# sch.net
KiCad netlist of a schematic drawn in EAGLE
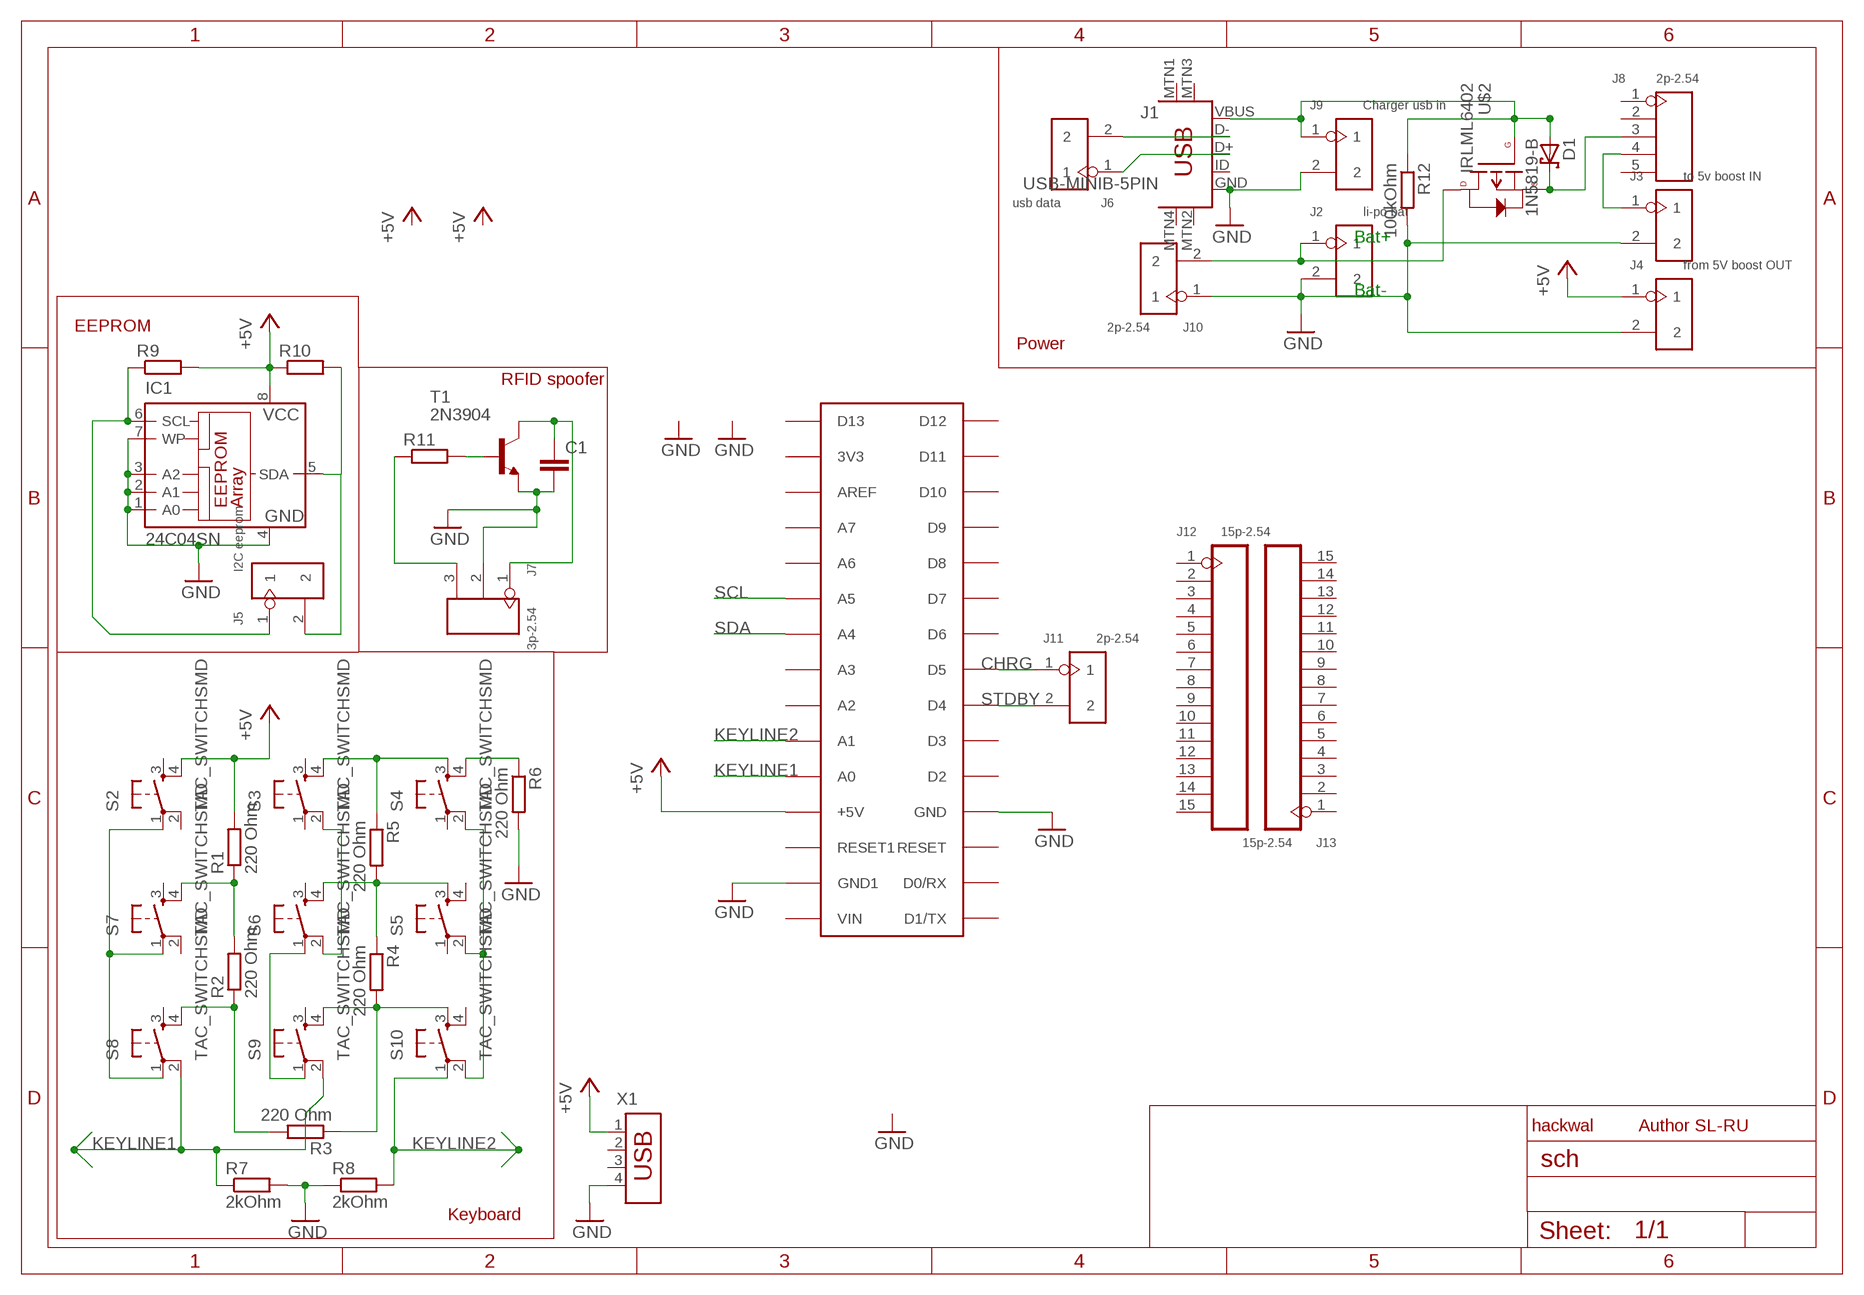
[diagram p0: schematic, sheet 1]

(export (version "E")
  (design (tool "Eeschema 10.0.6"))
  (components
    (comp (ref "C1")
      (value "C5/3")
      (footprint "eagle-import:C5B3")
      (libsource (lib "eagle-import") (part "C5/3"))
    )
    (comp (ref "D1")
      (value "1N5819-B")
      (footprint "eagle-import:DO41-7.6")
      (libsource (lib "eagle-import") (part "1N5819-B"))
    )
    (comp (ref "IC1")
      (value "24C04SN")
      (footprint "eagle-import:SO-08")
      (fields (field (name "MPN") "M24C04-WMN6P"))
      (libsource (lib "eagle-import") (part "24CSN04"))
    )
    (comp (ref "J1")
      (value "USB-MINIB-5PIN")
      (footprint "eagle-import:USB-MINIB")
      (libsource (lib "eagle-import") (part "USB-MINIB-5PIN"))
    )
    (comp (ref "J2")
      (value "li-po bat")
      (footprint "eagle-import:H2-2.54")
      (fields (field (name "MPN") "P125-1102A0BS116A1"))
      (libsource (lib "eagle-import") (part "DIP-BLACK-MALE-HEADER-VERT(2P-2.54)"))
    )
    (comp (ref "J3")
      (value "to 5v boost IN")
      (footprint "eagle-import:H2-2.54")
      (fields (field (name "MPN") "F185-1102A1BSYA1"))
      (libsource (lib "eagle-import") (part "DIP-BLACK-FEMALE-HEADER-VERT(2P-2.54)"))
    )
    (comp (ref "J4")
      (value "from 5V boost OUT")
      (footprint "eagle-import:H2-2.54")
      (fields (field (name "MPN") "F185-1102A1BSYA1"))
      (libsource (lib "eagle-import") (part "DIP-BLACK-FEMALE-HEADER-VERT(2P-2.54)"))
    )
    (comp (ref "J5")
      (value "I2C eeprom")
      (footprint "eagle-import:H2-2.54")
      (fields (field (name "MPN") "F185-1102A1BSYA1"))
      (libsource (lib "eagle-import") (part "DIP-BLACK-FEMALE-HEADER-VERT(2P-2.54)"))
    )
    (comp (ref "J6")
      (value "usb data")
      (footprint "eagle-import:H2-2.54")
      (fields (field (name "MPN") "F185-1102A1BSYA1"))
      (libsource (lib "eagle-import") (part "DIP-BLACK-FEMALE-HEADER-VERT(2P-2.54)"))
    )
    (comp (ref "J7")
      (value "3p-2.54")
      (footprint "eagle-import:H3-2.54")
      (fields (field (name "MPN") "F185-1103A0BSYA1"))
      (libsource (lib "eagle-import") (part "DIP-BLACK-FEMALE-HEADER-VERT(3P-2.54)"))
    )
    (comp (ref "J8")
      (value "2p-2.54")
      (footprint "eagle-import:H5-2.54")
      (libsource (lib "eagle-import") (part "DIP-BLACK-MALE-HEADER-VERT(5P-2.54)"))
    )
    (comp (ref "J9")
      (value "Charger usb in")
      (footprint "eagle-import:H2-2.54")
      (fields (field (name "MPN") "P125-1102A0BS116A1"))
      (libsource (lib "eagle-import") (part "DIP-BLACK-MALE-HEADER-VERT(2P-2.54)"))
    )
    (comp (ref "J10")
      (value "2p-2.54")
      (footprint "eagle-import:H2-2.54")
      (fields (field (name "MPN") "P125-1102A0BS116A1"))
      (libsource (lib "eagle-import") (part "DIP-BLACK-MALE-HEADER-VERT(2P-2.54)"))
    )
    (comp (ref "J11")
      (value "2p-2.54")
      (footprint "eagle-import:H2-2.54")
      (fields (field (name "MPN") "P125-1102A0BS116A1"))
      (libsource (lib "eagle-import") (part "DIP-BLACK-MALE-HEADER-VERT(2P-2.54)"))
    )
    (comp (ref "J12")
      (value "15p-2.54")
      (footprint "eagle-import:H15-2.54")
      (libsource (lib "eagle-import") (part "DIP-BLACK-FEMALE-HEADER-VERT(15P-2.54)"))
    )
    (comp (ref "J13")
      (value "15p-2.54")
      (footprint "eagle-import:H15-2.54")
      (libsource (lib "eagle-import") (part "DIP-BLACK-FEMALE-HEADER-VERT(15P-2.54)"))
    )
    (comp (ref "R1")
      (value "220 Ohm")
      (footprint "eagle-import:0207_10")
      (libsource (lib "eagle-import") (part "R-EU_0207/10"))
    )
    (comp (ref "R2")
      (value "220 Ohm")
      (footprint "eagle-import:0207_10")
      (libsource (lib "eagle-import") (part "R-EU_0207/10"))
    )
    (comp (ref "R3")
      (value "220 Ohm")
      (footprint "eagle-import:0207_10")
      (libsource (lib "eagle-import") (part "R-EU_0207/10"))
    )
    (comp (ref "R4")
      (value "220 Ohm")
      (footprint "eagle-import:0207_10")
      (libsource (lib "eagle-import") (part "R-EU_0207/10"))
    )
    (comp (ref "R5")
      (value "220 Ohm")
      (footprint "eagle-import:0207_10")
      (libsource (lib "eagle-import") (part "R-EU_0207/10"))
    )
    (comp (ref "R6")
      (value "220 Ohm")
      (footprint "eagle-import:0207_10")
      (libsource (lib "eagle-import") (part "R-EU_0207/10"))
    )
    (comp (ref "R7")
      (value "2kOhm")
      (footprint "eagle-import:0207_10")
      (libsource (lib "eagle-import") (part "R-EU_0207/10"))
    )
    (comp (ref "R8")
      (value "2kOhm")
      (footprint "eagle-import:0207_10")
      (libsource (lib "eagle-import") (part "R-EU_0207/10"))
    )
    (comp (ref "R9")
      (value "R-EU_0207/10")
      (footprint "eagle-import:0207_10")
      (libsource (lib "eagle-import") (part "R-EU_0207/10"))
    )
    (comp (ref "R10")
      (value "R-EU_0207/10")
      (footprint "eagle-import:0207_10")
      (libsource (lib "eagle-import") (part "R-EU_0207/10"))
    )
    (comp (ref "R11")
      (value "R-EU_0207/10")
      (footprint "eagle-import:0207_10")
      (libsource (lib "eagle-import") (part "R-EU_0207/10"))
    )
    (comp (ref "R12")
      (value "100kOhm")
      (footprint "eagle-import:0207_10")
      (libsource (lib "eagle-import") (part "R-EU_0207/10"))
    )
    (comp (ref "S2")
      (value "TAC_SWITCHSMD")
      (footprint "eagle-import:TACTILE-SWITCH-SMD")
      (libsource (lib "eagle-import") (part "TAC_SWITCHSMD"))
    )
    (comp (ref "S3")
      (value "TAC_SWITCHSMD")
      (footprint "eagle-import:TACTILE-SWITCH-SMD")
      (libsource (lib "eagle-import") (part "TAC_SWITCHSMD"))
    )
    (comp (ref "S4")
      (value "TAC_SWITCHSMD")
      (footprint "eagle-import:TACTILE-SWITCH-SMD")
      (libsource (lib "eagle-import") (part "TAC_SWITCHSMD"))
    )
    (comp (ref "S5")
      (value "TAC_SWITCHSMD")
      (footprint "eagle-import:TACTILE-SWITCH-SMD")
      (libsource (lib "eagle-import") (part "TAC_SWITCHSMD"))
    )
    (comp (ref "S6")
      (value "TAC_SWITCHSMD")
      (footprint "eagle-import:TACTILE-SWITCH-SMD")
      (libsource (lib "eagle-import") (part "TAC_SWITCHSMD"))
    )
    (comp (ref "S7")
      (value "TAC_SWITCHSMD")
      (footprint "eagle-import:TACTILE-SWITCH-SMD")
      (libsource (lib "eagle-import") (part "TAC_SWITCHSMD"))
    )
    (comp (ref "S8")
      (value "TAC_SWITCHSMD")
      (footprint "eagle-import:TACTILE-SWITCH-SMD")
      (libsource (lib "eagle-import") (part "TAC_SWITCHSMD"))
    )
    (comp (ref "S9")
      (value "TAC_SWITCHSMD")
      (footprint "eagle-import:TACTILE-SWITCH-SMD")
      (libsource (lib "eagle-import") (part "TAC_SWITCHSMD"))
    )
    (comp (ref "S10")
      (value "TAC_SWITCHSMD")
      (footprint "eagle-import:TACTILE-SWITCH-SMD")
      (libsource (lib "eagle-import") (part "TAC_SWITCHSMD"))
    )
    (comp (ref "T1")
      (value "2N3904")
      (footprint "eagle-import:TO92")
      (libsource (lib "eagle-import") (part "2N3904"))
    )
    (comp (ref "U$1")
      (value "ARDUINONANO")
      (footprint "eagle-import:PDIP-32")
      (libsource (lib "eagle-import") (part "ARDUINONANO"))
    )
    (comp (ref "U$2")
      (value "IRLML6402")
      (footprint "eagle-import:SOT23-3")
      (libsource (lib "eagle-import") (part "P-CHANNEL-MOSFET"))
    )
    (comp (ref "X1")
      (value "USB-787616")
      (footprint "eagle-import:USB")
      (libsource (lib "eagle-import") (part "USB-787616"))
    )
  )
  (nets
    (net (code "1") (name "+5V") (class "Default")
      (node (ref "IC1") (pin "8") (pinfunction "VCC_8") (pintype "power_in"))
      (node (ref "J4") (pin "1") (pinfunction "1_1") (pintype "bidirectional"))
      (node (ref "R1") (pin "2") (pinfunction "2_2") (pintype "passive"))
      (node (ref "R10") (pin "1") (pinfunction "1_1") (pintype "passive"))
      (node (ref "R9") (pin "2") (pinfunction "2_2") (pintype "passive"))
      (node (ref "S2") (pin "4") (pinfunction "4_4") (pintype "passive"))
      (node (ref "U$1") (pin "+5V") (pinfunction "+5V_+5V") (pintype "bidirectional"))
      (node (ref "X1") (pin "1") (pinfunction "1_1") (pintype "passive"))
    )
    (net (code "2") (name "/CHRG") (class "Default")
      (node (ref "J11") (pin "1") (pinfunction "1_1") (pintype "bidirectional"))
      (node (ref "U$1") (pin "D5") (pinfunction "D5_D5") (pintype "bidirectional"))
    )
    (net (code "3") (name "/KEYLINE1") (class "Default")
      (node (ref "R7") (pin "1") (pinfunction "1_1") (pintype "passive"))
      (node (ref "S8") (pin "2") (pinfunction "2_2") (pintype "passive"))
      (node (ref "S9") (pin "2") (pinfunction "2_2") (pintype "passive"))
      (node (ref "U$1") (pin "A0") (pinfunction "A0_A0") (pintype "bidirectional"))
    )
    (net (code "4") (name "/KEYLINE2") (class "Default")
      (node (ref "R8") (pin "2") (pinfunction "2_2") (pintype "passive"))
      (node (ref "S10") (pin "1") (pinfunction "1_1") (pintype "passive"))
      (node (ref "U$1") (pin "A1") (pinfunction "A1_A1") (pintype "bidirectional"))
    )
    (net (code "5") (name "/SCL") (class "Default")
      (node (ref "U$1") (pin "A5") (pinfunction "A5_A5") (pintype "bidirectional"))
    )
    (net (code "6") (name "/SDA") (class "Default")
      (node (ref "U$1") (pin "A4") (pinfunction "A4_A4") (pintype "bidirectional"))
    )
    (net (code "7") (name "/STDBY") (class "Default")
      (node (ref "J11") (pin "2") (pinfunction "2_2") (pintype "bidirectional"))
      (node (ref "U$1") (pin "D4") (pinfunction "D4_D4") (pintype "bidirectional"))
    )
    (net (code "8") (name "GND") (class "Default")
      (node (ref "C1") (pin "2") (pinfunction "2_2") (pintype "passive"))
      (node (ref "IC1") (pin "1") (pinfunction "A0_1") (pintype "input"))
      (node (ref "IC1") (pin "2") (pinfunction "A1_2") (pintype "input"))
      (node (ref "IC1") (pin "3") (pinfunction "A2_3") (pintype "input"))
      (node (ref "IC1") (pin "4") (pinfunction "GND_4") (pintype "power_in"))
      (node (ref "IC1") (pin "7") (pinfunction "WP_7") (pintype "input"))
      (node (ref "J1") (pin "GND") (pinfunction "GND_GND") (pintype "bidirectional"))
      (node (ref "J10") (pin "1") (pinfunction "1_1") (pintype "bidirectional"))
      (node (ref "J2") (pin "2") (pinfunction "2_2") (pintype "bidirectional"))
      (node (ref "J3") (pin "2") (pinfunction "2_2") (pintype "bidirectional"))
      (node (ref "J4") (pin "2") (pinfunction "2_2") (pintype "bidirectional"))
      (node (ref "J7") (pin "2") (pinfunction "P$2_2") (pintype "bidirectional"))
      (node (ref "J9") (pin "2") (pinfunction "2_2") (pintype "bidirectional"))
      (node (ref "R12") (pin "2") (pinfunction "2_2") (pintype "passive"))
      (node (ref "R6") (pin "2") (pinfunction "2_2") (pintype "passive"))
      (node (ref "R7") (pin "2") (pinfunction "2_2") (pintype "passive"))
      (node (ref "R8") (pin "1") (pinfunction "1_1") (pintype "passive"))
      (node (ref "T1") (pin "3") (pinfunction "E_3") (pintype "passive"))
      (node (ref "U$1") (pin "GND") (pinfunction "GND_GND") (pintype "bidirectional"))
      (node (ref "U$1") (pin "GND1") (pinfunction "GND1_GND1") (pintype "bidirectional"))
      (node (ref "X1") (pin "4") (pinfunction "4_4") (pintype "passive"))
    )
    (net (code "9") (name "Net-(IC1-SCL)") (class "Default")
      (node (ref "IC1") (pin "6") (pinfunction "SCL_6") (pintype "input"))
      (node (ref "J5") (pin "1") (pinfunction "1_1") (pintype "bidirectional"))
      (node (ref "R9") (pin "1") (pinfunction "1_1") (pintype "passive"))
    )
    (net (code "10") (name "Net-(IC1-SDA)") (class "Default")
      (node (ref "IC1") (pin "5") (pinfunction "SDA_5") (pintype "bidirectional"))
      (node (ref "J5") (pin "2") (pinfunction "2_2") (pintype "bidirectional"))
      (node (ref "R10") (pin "2") (pinfunction "2_2") (pintype "passive"))
    )
    (net (code "11") (name "Net-(J1-PadD+)") (class "Default")
      (node (ref "J1") (pin "D+") (pinfunction "D+_D+") (pintype "bidirectional"))
      (node (ref "J6") (pin "1") (pinfunction "1_1") (pintype "bidirectional"))
    )
    (net (code "12") (name "Net-(J1-PadD-)") (class "Default")
      (node (ref "J1") (pin "D-") (pinfunction "D-_D-") (pintype "bidirectional"))
      (node (ref "J6") (pin "2") (pinfunction "2_2") (pintype "bidirectional"))
    )
    (net (code "13") (name "Net-(J3-Pad1)") (class "Default")
      (node (ref "J3") (pin "1") (pinfunction "1_1") (pintype "bidirectional"))
      (node (ref "J8") (pin "4") (pinfunction "4_4") (pintype "bidirectional"))
    )
    (net (code "14") (name "Net-(J7-P$1)") (class "Default")
      (node (ref "C1") (pin "1") (pinfunction "1_1") (pintype "passive"))
      (node (ref "J7") (pin "1") (pinfunction "P$1_1") (pintype "bidirectional"))
      (node (ref "T1") (pin "1") (pinfunction "C_1") (pintype "passive"))
    )
    (net (code "15") (name "Net-(J7-P$3)") (class "Default")
      (node (ref "J7") (pin "3") (pinfunction "P$3_3") (pintype "bidirectional"))
      (node (ref "R11") (pin "1") (pinfunction "1_1") (pintype "passive"))
    )
    (net (code "16") (name "Net-(R1-Pad1)") (class "Default")
      (node (ref "R1") (pin "1") (pinfunction "1_1") (pintype "passive"))
      (node (ref "R2") (pin "2") (pinfunction "2_2") (pintype "passive"))
      (node (ref "S7") (pin "4") (pinfunction "4_4") (pintype "passive"))
    )
    (net (code "17") (name "Net-(R2-Pad1)") (class "Default")
      (node (ref "R2") (pin "1") (pinfunction "1_1") (pintype "passive"))
      (node (ref "R3") (pin "2") (pinfunction "2_2") (pintype "passive"))
      (node (ref "S8") (pin "4") (pinfunction "4_4") (pintype "passive"))
    )
    (net (code "18") (name "Net-(R3-Pad1)") (class "Default")
      (node (ref "R3") (pin "1") (pinfunction "1_1") (pintype "passive"))
      (node (ref "R4") (pin "2") (pinfunction "2_2") (pintype "passive"))
      (node (ref "S10") (pin "3") (pinfunction "3_3") (pintype "passive"))
      (node (ref "S9") (pin "4") (pinfunction "4_4") (pintype "passive"))
    )
    (net (code "19") (name "Net-(R4-Pad1)") (class "Default")
      (node (ref "R4") (pin "1") (pinfunction "1_1") (pintype "passive"))
      (node (ref "R5") (pin "2") (pinfunction "2_2") (pintype "passive"))
      (node (ref "S5") (pin "3") (pinfunction "3_3") (pintype "passive"))
      (node (ref "S6") (pin "4") (pinfunction "4_4") (pintype "passive"))
    )
    (net (code "20") (name "Net-(R5-Pad1)") (class "Default")
      (node (ref "R5") (pin "1") (pinfunction "1_1") (pintype "passive"))
      (node (ref "S3") (pin "4") (pinfunction "4_4") (pintype "passive"))
      (node (ref "S4") (pin "3") (pinfunction "3_3") (pintype "passive"))
    )
    (net (code "21") (name "Net-(R6-Pad1)") (class "Default")
      (node (ref "R6") (pin "1") (pinfunction "1_1") (pintype "passive"))
      (node (ref "S4") (pin "4") (pinfunction "4_4") (pintype "passive"))
    )
    (net (code "22") (name "Net-(S2-Pad1)") (class "Default")
      (node (ref "S2") (pin "1") (pinfunction "1_1") (pintype "passive"))
      (node (ref "S7") (pin "1") (pinfunction "1_1") (pintype "passive"))
      (node (ref "S8") (pin "1") (pinfunction "1_1") (pintype "passive"))
    )
    (net (code "23") (name "Net-(S3-Pad2)") (class "Default")
      (node (ref "S3") (pin "2") (pinfunction "2_2") (pintype "passive"))
      (node (ref "S6") (pin "2") (pinfunction "2_2") (pintype "passive"))
    )
    (net (code "24") (name "Net-(S6-Pad1)") (class "Default")
      (node (ref "S6") (pin "1") (pinfunction "1_1") (pintype "passive"))
      (node (ref "S9") (pin "1") (pinfunction "1_1") (pintype "passive"))
    )
    (net (code "25") (name "Net-(S10-Pad2)") (class "Default")
      (node (ref "S10") (pin "2") (pinfunction "2_2") (pintype "passive"))
      (node (ref "S4") (pin "2") (pinfunction "2_2") (pintype "passive"))
      (node (ref "S5") (pin "2") (pinfunction "2_2") (pintype "passive"))
    )
    (net (code "26") (name "Net-(T1-B)") (class "Default")
      (node (ref "R11") (pin "2") (pinfunction "2_2") (pintype "passive"))
      (node (ref "T1") (pin "2") (pinfunction "B_2") (pintype "passive"))
    )
    (net (code "27") (name "Net-(U$2-D)") (class "Default")
      (node (ref "J10") (pin "2") (pinfunction "2_2") (pintype "bidirectional"))
      (node (ref "J2") (pin "1") (pinfunction "1_1") (pintype "bidirectional"))
      (node (ref "U$2") (pin "3") (pinfunction "D_3") (pintype "passive"))
    )
    (net (code "28") (name "Net-(U$2-G)") (class "Default")
      (node (ref "D1") (pin "A") (pinfunction "A_A") (pintype "passive"))
      (node (ref "J1") (pin "VBUS") (pinfunction "VBUS_VBUS") (pintype "bidirectional"))
      (node (ref "J9") (pin "1") (pinfunction "1_1") (pintype "bidirectional"))
      (node (ref "R12") (pin "1") (pinfunction "1_1") (pintype "passive"))
      (node (ref "U$2") (pin "1") (pinfunction "G_1") (pintype "passive"))
    )
    (net (code "29") (name "Net-(U$2-S)") (class "Default")
      (node (ref "D1") (pin "C") (pinfunction "C_C") (pintype "passive"))
      (node (ref "J8") (pin "3") (pinfunction "3_3") (pintype "bidirectional"))
      (node (ref "U$2") (pin "2") (pinfunction "S_2") (pintype "passive"))
    )
    (net (code "30") (name "unconnected-(J1-MTN1-PadMTN3)") (class "Default")
      (node (ref "J1") (pin "MTN3") (pinfunction "MTN1_MTN3") (pintype "bidirectional"))
    )
    (net (code "31") (name "unconnected-(J1-MTN2-PadMTN1)") (class "Default")
      (node (ref "J1") (pin "MTN1") (pinfunction "MTN2_MTN1") (pintype "bidirectional"))
    )
    (net (code "32") (name "unconnected-(J1-MTN3-PadMTN2)") (class "Default")
      (node (ref "J1") (pin "MTN2") (pinfunction "MTN3_MTN2") (pintype "bidirectional"))
    )
    (net (code "33") (name "unconnected-(J1-PadID)") (class "Default")
      (node (ref "J1") (pin "ID") (pinfunction "ID_ID") (pintype "bidirectional"))
    )
    (net (code "34") (name "unconnected-(J1-PadMTN4)") (class "Default")
      (node (ref "J1") (pin "MTN4") (pinfunction "MTN4_MTN4") (pintype "bidirectional"))
    )
    (net (code "35") (name "unconnected-(J8-Pad1)") (class "Default")
      (node (ref "J8") (pin "1") (pinfunction "1_1") (pintype "bidirectional"))
    )
    (net (code "36") (name "unconnected-(J8-Pad2)") (class "Default")
      (node (ref "J8") (pin "2") (pinfunction "2_2") (pintype "bidirectional"))
    )
    (net (code "37") (name "unconnected-(J8-Pad5)") (class "Default")
      (node (ref "J8") (pin "5") (pinfunction "5_5") (pintype "bidirectional"))
    )
    (net (code "38") (name "unconnected-(J12-Pad1)") (class "Default")
      (node (ref "J12") (pin "1") (pinfunction "1_1") (pintype "passive"))
    )
    (net (code "39") (name "unconnected-(J12-Pad2)") (class "Default")
      (node (ref "J12") (pin "2") (pinfunction "2_2") (pintype "passive"))
    )
    (net (code "40") (name "unconnected-(J12-Pad3)") (class "Default")
      (node (ref "J12") (pin "3") (pinfunction "3_3") (pintype "passive"))
    )
    (net (code "41") (name "unconnected-(J12-Pad4)") (class "Default")
      (node (ref "J12") (pin "4") (pinfunction "4_4") (pintype "passive"))
    )
    (net (code "42") (name "unconnected-(J12-Pad5)") (class "Default")
      (node (ref "J12") (pin "5") (pinfunction "5_5") (pintype "passive"))
    )
    (net (code "43") (name "unconnected-(J12-Pad6)") (class "Default")
      (node (ref "J12") (pin "6") (pinfunction "6_6") (pintype "passive"))
    )
    (net (code "44") (name "unconnected-(J12-Pad7)") (class "Default")
      (node (ref "J12") (pin "7") (pinfunction "7_7") (pintype "passive"))
    )
    (net (code "45") (name "unconnected-(J12-Pad8)") (class "Default")
      (node (ref "J12") (pin "8") (pinfunction "8_8") (pintype "passive"))
    )
    (net (code "46") (name "unconnected-(J12-Pad9)") (class "Default")
      (node (ref "J12") (pin "9") (pinfunction "9_9") (pintype "passive"))
    )
    (net (code "47") (name "unconnected-(J12-Pad10)") (class "Default")
      (node (ref "J12") (pin "10") (pinfunction "10_10") (pintype "passive"))
    )
    (net (code "48") (name "unconnected-(J12-Pad11)") (class "Default")
      (node (ref "J12") (pin "11") (pinfunction "11_11") (pintype "passive"))
    )
    (net (code "49") (name "unconnected-(J12-Pad12)") (class "Default")
      (node (ref "J12") (pin "12") (pinfunction "12_12") (pintype "passive"))
    )
    (net (code "50") (name "unconnected-(J12-Pad13)") (class "Default")
      (node (ref "J12") (pin "13") (pinfunction "13_13") (pintype "passive"))
    )
    (net (code "51") (name "unconnected-(J12-Pad14)") (class "Default")
      (node (ref "J12") (pin "14") (pinfunction "14_14") (pintype "passive"))
    )
    (net (code "52") (name "unconnected-(J12-Pad15)") (class "Default")
      (node (ref "J12") (pin "15") (pinfunction "15_15") (pintype "passive"))
    )
    (net (code "53") (name "unconnected-(J13-Pad1)") (class "Default")
      (node (ref "J13") (pin "1") (pinfunction "1_1") (pintype "passive"))
    )
    (net (code "54") (name "unconnected-(J13-Pad2)") (class "Default")
      (node (ref "J13") (pin "2") (pinfunction "2_2") (pintype "passive"))
    )
    (net (code "55") (name "unconnected-(J13-Pad3)") (class "Default")
      (node (ref "J13") (pin "3") (pinfunction "3_3") (pintype "passive"))
    )
    (net (code "56") (name "unconnected-(J13-Pad4)") (class "Default")
      (node (ref "J13") (pin "4") (pinfunction "4_4") (pintype "passive"))
    )
    (net (code "57") (name "unconnected-(J13-Pad5)") (class "Default")
      (node (ref "J13") (pin "5") (pinfunction "5_5") (pintype "passive"))
    )
    (net (code "58") (name "unconnected-(J13-Pad6)") (class "Default")
      (node (ref "J13") (pin "6") (pinfunction "6_6") (pintype "passive"))
    )
    (net (code "59") (name "unconnected-(J13-Pad7)") (class "Default")
      (node (ref "J13") (pin "7") (pinfunction "7_7") (pintype "passive"))
    )
    (net (code "60") (name "unconnected-(J13-Pad8)") (class "Default")
      (node (ref "J13") (pin "8") (pinfunction "8_8") (pintype "passive"))
    )
    (net (code "61") (name "unconnected-(J13-Pad9)") (class "Default")
      (node (ref "J13") (pin "9") (pinfunction "9_9") (pintype "passive"))
    )
    (net (code "62") (name "unconnected-(J13-Pad10)") (class "Default")
      (node (ref "J13") (pin "10") (pinfunction "10_10") (pintype "passive"))
    )
    (net (code "63") (name "unconnected-(J13-Pad11)") (class "Default")
      (node (ref "J13") (pin "11") (pinfunction "11_11") (pintype "passive"))
    )
    (net (code "64") (name "unconnected-(J13-Pad12)") (class "Default")
      (node (ref "J13") (pin "12") (pinfunction "12_12") (pintype "passive"))
    )
    (net (code "65") (name "unconnected-(J13-Pad13)") (class "Default")
      (node (ref "J13") (pin "13") (pinfunction "13_13") (pintype "passive"))
    )
    (net (code "66") (name "unconnected-(J13-Pad14)") (class "Default")
      (node (ref "J13") (pin "14") (pinfunction "14_14") (pintype "passive"))
    )
    (net (code "67") (name "unconnected-(J13-Pad15)") (class "Default")
      (node (ref "J13") (pin "15") (pinfunction "15_15") (pintype "passive"))
    )
    (net (code "68") (name "unconnected-(S2-Pad2)") (class "Default")
      (node (ref "S2") (pin "2") (pinfunction "2_2") (pintype "passive"))
    )
    (net (code "69") (name "unconnected-(S2-Pad3)") (class "Default")
      (node (ref "S2") (pin "3") (pinfunction "3_3") (pintype "passive"))
    )
    (net (code "70") (name "unconnected-(S3-Pad1)") (class "Default")
      (node (ref "S3") (pin "1") (pinfunction "1_1") (pintype "passive"))
    )
    (net (code "71") (name "unconnected-(S3-Pad3)") (class "Default")
      (node (ref "S3") (pin "3") (pinfunction "3_3") (pintype "passive"))
    )
    (net (code "72") (name "unconnected-(S4-Pad1)") (class "Default")
      (node (ref "S4") (pin "1") (pinfunction "1_1") (pintype "passive"))
    )
    (net (code "73") (name "unconnected-(S5-Pad1)") (class "Default")
      (node (ref "S5") (pin "1") (pinfunction "1_1") (pintype "passive"))
    )
    (net (code "74") (name "unconnected-(S5-Pad4)") (class "Default")
      (node (ref "S5") (pin "4") (pinfunction "4_4") (pintype "passive"))
    )
    (net (code "75") (name "unconnected-(S6-Pad3)") (class "Default")
      (node (ref "S6") (pin "3") (pinfunction "3_3") (pintype "passive"))
    )
    (net (code "76") (name "unconnected-(S7-Pad2)") (class "Default")
      (node (ref "S7") (pin "2") (pinfunction "2_2") (pintype "passive"))
    )
    (net (code "77") (name "unconnected-(S7-Pad3)") (class "Default")
      (node (ref "S7") (pin "3") (pinfunction "3_3") (pintype "passive"))
    )
    (net (code "78") (name "unconnected-(S8-Pad3)") (class "Default")
      (node (ref "S8") (pin "3") (pinfunction "3_3") (pintype "passive"))
    )
    (net (code "79") (name "unconnected-(S9-Pad3)") (class "Default")
      (node (ref "S9") (pin "3") (pinfunction "3_3") (pintype "passive"))
    )
    (net (code "80") (name "unconnected-(S10-Pad4)") (class "Default")
      (node (ref "S10") (pin "4") (pinfunction "4_4") (pintype "passive"))
    )
    (net (code "81") (name "unconnected-(U$1-Pad3V3)") (class "Default")
      (node (ref "U$1") (pin "3V3") (pinfunction "3V3_3V3") (pintype "bidirectional"))
    )
    (net (code "82") (name "unconnected-(U$1-PadA2)") (class "Default")
      (node (ref "U$1") (pin "A2") (pinfunction "A2_A2") (pintype "bidirectional"))
    )
    (net (code "83") (name "unconnected-(U$1-PadA3)") (class "Default")
      (node (ref "U$1") (pin "A3") (pinfunction "A3_A3") (pintype "bidirectional"))
    )
    (net (code "84") (name "unconnected-(U$1-PadA6)") (class "Default")
      (node (ref "U$1") (pin "A6") (pinfunction "A6_A6") (pintype "bidirectional"))
    )
    (net (code "85") (name "unconnected-(U$1-PadA7)") (class "Default")
      (node (ref "U$1") (pin "A7") (pinfunction "A7_A7") (pintype "bidirectional"))
    )
    (net (code "86") (name "unconnected-(U$1-PadAREF)") (class "Default")
      (node (ref "U$1") (pin "AREF") (pinfunction "AREF_AREF") (pintype "bidirectional"))
    )
    (net (code "87") (name "unconnected-(U$1-PadD0{slash}RX)") (class "Default")
      (node (ref "U$1") (pin "D0/RX") (pinfunction "D0/RX_D0/RX") (pintype "bidirectional"))
    )
    (net (code "88") (name "unconnected-(U$1-PadD1{slash}TX)") (class "Default")
      (node (ref "U$1") (pin "D1/TX") (pinfunction "D1/TX_D1/TX") (pintype "bidirectional"))
    )
    (net (code "89") (name "unconnected-(U$1-PadD2)") (class "Default")
      (node (ref "U$1") (pin "D2") (pinfunction "D2_D2") (pintype "bidirectional"))
    )
    (net (code "90") (name "unconnected-(U$1-PadD3)") (class "Default")
      (node (ref "U$1") (pin "D3") (pinfunction "D3_D3") (pintype "bidirectional"))
    )
    (net (code "91") (name "unconnected-(U$1-PadD6)") (class "Default")
      (node (ref "U$1") (pin "D6") (pinfunction "D6_D6") (pintype "bidirectional"))
    )
    (net (code "92") (name "unconnected-(U$1-PadD7)") (class "Default")
      (node (ref "U$1") (pin "D7") (pinfunction "D7_D7") (pintype "bidirectional"))
    )
    (net (code "93") (name "unconnected-(U$1-PadD8)") (class "Default")
      (node (ref "U$1") (pin "D8") (pinfunction "D8_D8") (pintype "bidirectional"))
    )
    (net (code "94") (name "unconnected-(U$1-PadD9)") (class "Default")
      (node (ref "U$1") (pin "D9") (pinfunction "D9_D9") (pintype "bidirectional"))
    )
    (net (code "95") (name "unconnected-(U$1-PadD10)") (class "Default")
      (node (ref "U$1") (pin "D10") (pinfunction "D10_D10") (pintype "bidirectional"))
    )
    (net (code "96") (name "unconnected-(U$1-PadD11)") (class "Default")
      (node (ref "U$1") (pin "D11") (pinfunction "D11_D11") (pintype "bidirectional"))
    )
    (net (code "97") (name "unconnected-(U$1-PadD12)") (class "Default")
      (node (ref "U$1") (pin "D12") (pinfunction "D12_D12") (pintype "bidirectional"))
    )
    (net (code "98") (name "unconnected-(U$1-PadD13)") (class "Default")
      (node (ref "U$1") (pin "D13") (pinfunction "D13_D13") (pintype "bidirectional"))
    )
    (net (code "99") (name "unconnected-(U$1-PadRESET)") (class "Default")
      (node (ref "U$1") (pin "RESET") (pinfunction "RESET_RESET") (pintype "bidirectional"))
    )
    (net (code "100") (name "unconnected-(U$1-PadRESET1)") (class "Default")
      (node (ref "U$1") (pin "RESET1") (pinfunction "RESET1_RESET1") (pintype "bidirectional"))
    )
    (net (code "101") (name "unconnected-(U$1-PadVIN)") (class "Default")
      (node (ref "U$1") (pin "VIN") (pinfunction "VIN_VIN") (pintype "bidirectional"))
    )
    (net (code "102") (name "unconnected-(X1-Pad2)") (class "Default")
      (node (ref "X1") (pin "2") (pinfunction "2_2") (pintype "passive"))
    )
    (net (code "103") (name "unconnected-(X1-Pad3)") (class "Default")
      (node (ref "X1") (pin "3") (pinfunction "3_3") (pintype "passive"))
    )
  )
)
